# BSPD_Test_Board_rev2.net
KiCad netlist of a schematic drawn in EAGLE
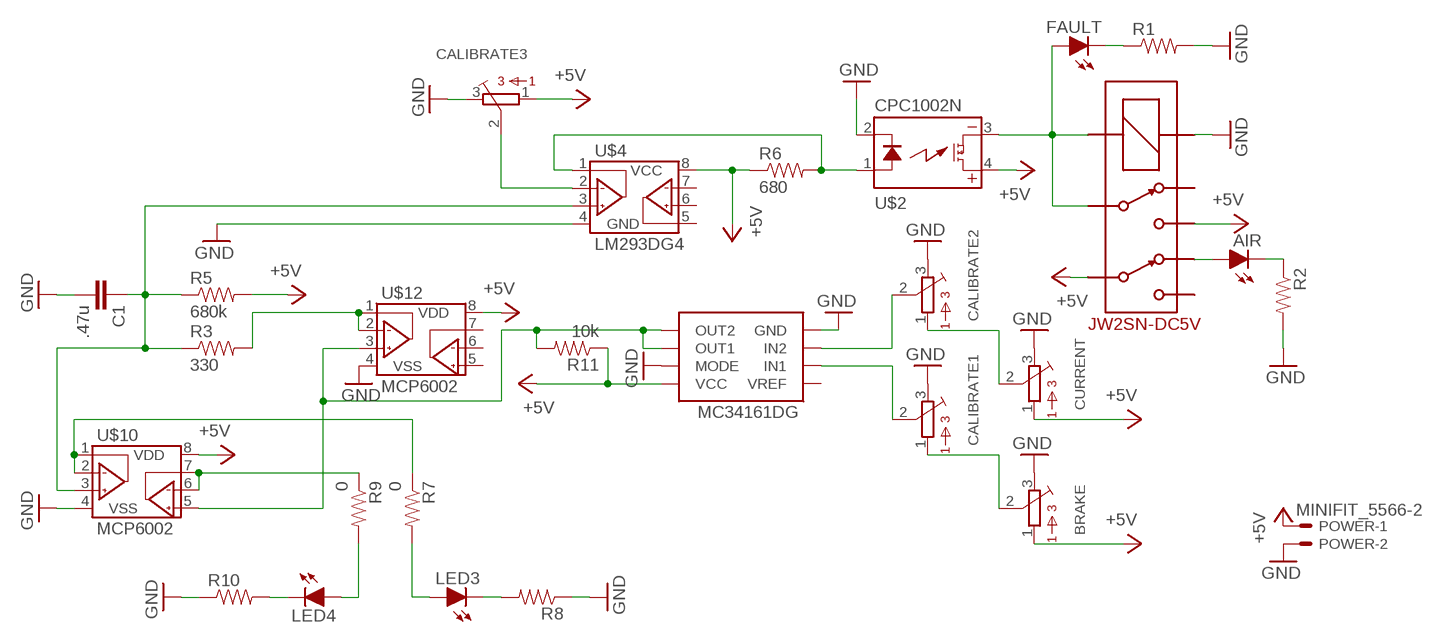
[diagram p0: schematic, sheet 1]

(export (version "E")
  (design (tool "Eeschema 10.0.6"))
  (components
    (comp (ref "AIR")
      (value "LED-5MM")
      (footprint "eagle-import:LED-5MM")
      (libsource (lib "eagle-import") (part "LED-5MM"))
    )
    (comp (ref "BRAKE")
      (value "TRIMPOT_3296C")
      (footprint "eagle-import:TRIMPOT_3296")
      (libsource (lib "eagle-import") (part "TRIMPOT_3296C"))
    )
    (comp (ref "C1")
      (value ".47u")
      (footprint "eagle-import:CAP-PTH-SMALLEZ")
      (libsource (lib "eagle-import") (part "CAPEZ"))
    )
    (comp (ref "CALIBRATE1")
      (value "TRIMPOT_3296C")
      (footprint "eagle-import:TRIMPOT_3296")
      (libsource (lib "eagle-import") (part "TRIMPOT_3296C"))
    )
    (comp (ref "CALIBRATE2")
      (value "TRIMPOT_3296C")
      (footprint "eagle-import:TRIMPOT_3296")
      (libsource (lib "eagle-import") (part "TRIMPOT_3296C"))
    )
    (comp (ref "CALIBRATE3")
      (value "TRIMPOT_3296C")
      (footprint "eagle-import:TRIMPOT_3296")
      (libsource (lib "eagle-import") (part "TRIMPOT_3296C"))
    )
    (comp (ref "CURRENT")
      (value "TRIMPOT_3296C")
      (footprint "eagle-import:TRIMPOT_3296")
      (libsource (lib "eagle-import") (part "TRIMPOT_3296C"))
    )
    (comp (ref "FAULT")
      (value "LED-5MM")
      (footprint "eagle-import:LED-5MM")
      (libsource (lib "eagle-import") (part "LED-5MM"))
    )
    (comp (ref "LED3")
      (value "LED-5MM")
      (footprint "eagle-import:LED-5MM")
      (libsource (lib "eagle-import") (part "LED-5MM"))
    )
    (comp (ref "LED4")
      (value "LED-5MM")
      (footprint "eagle-import:LED-5MM")
      (libsource (lib "eagle-import") (part "LED-5MM"))
    )
    (comp (ref "MC34161DG")
      (value "MC34161DG")
      (footprint "eagle-import:SOIC-08")
      (libsource (lib "eagle-import") (part "MC34161DG"))
    )
    (comp (ref "POWER")
      (value "MINIFIT_5566-2")
      (footprint "eagle-import:MINIFIT_5566-2")
      (libsource (lib "eagle-import") (part "MINIFIT_5566-2"))
    )
    (comp (ref "R1")
      (value "RESISTOR0805-RES")
      (footprint "eagle-import:0805")
      (libsource (lib "eagle-import") (part "RESISTOR0805-RES"))
    )
    (comp (ref "R2")
      (value "RESISTOR0805-RES")
      (footprint "eagle-import:0805")
      (libsource (lib "eagle-import") (part "RESISTOR0805-RES"))
    )
    (comp (ref "R3")
      (value "330")
      (footprint "eagle-import:AXIAL-0.3EZ")
      (libsource (lib "eagle-import") (part "RESISTOREZ"))
    )
    (comp (ref "R5")
      (value "680k")
      (footprint "eagle-import:AXIAL-0.3EZ")
      (libsource (lib "eagle-import") (part "RESISTOREZ"))
    )
    (comp (ref "R6")
      (value "680")
      (footprint "eagle-import:0805")
      (libsource (lib "eagle-import") (part "RESISTOR0805-RES"))
    )
    (comp (ref "R7")
      (value "0")
      (footprint "eagle-import:AXIAL-0.3EZ")
      (libsource (lib "eagle-import") (part "RESISTOREZ"))
    )
    (comp (ref "R8")
      (value "RESISTOR0805-RES")
      (footprint "eagle-import:0805")
      (libsource (lib "eagle-import") (part "RESISTOR0805-RES"))
    )
    (comp (ref "R9")
      (value "0")
      (footprint "eagle-import:AXIAL-0.3EZ")
      (libsource (lib "eagle-import") (part "RESISTOREZ"))
    )
    (comp (ref "R10")
      (value "RESISTOR0805-RES")
      (footprint "eagle-import:0805")
      (libsource (lib "eagle-import") (part "RESISTOR0805-RES"))
    )
    (comp (ref "R11")
      (value "10k")
      (footprint "eagle-import:0805")
      (libsource (lib "eagle-import") (part "RESISTOR0805-RES"))
    )
    (comp (ref "U$2")
      (value "CPC1002N")
      (footprint "eagle-import:SOP04")
      (libsource (lib "eagle-import") (part "CPC1002N"))
    )
    (comp (ref "U$3")
      (value "DPDT_RELAY_PANASONIC_JW2SN-DC5V")
      (footprint "eagle-import:DPDT_RELAY_PANASONIC_JW2SN")
      (libsource (lib "eagle-import") (part "DPDT_RELAY_PANASONIC_JW2SN-DC5V"))
    )
    (comp (ref "U$4")
      (value "LM293DG4")
      (footprint "eagle-import:SOIC-08")
      (libsource (lib "eagle-import") (part "LM293DG4"))
    )
    (comp (ref "U$10")
      (value "MCP6002")
      (footprint "eagle-import:SOIC-08")
      (libsource (lib "eagle-import") (part "MCP6002"))
    )
    (comp (ref "U$12")
      (value "MCP6002")
      (footprint "eagle-import:SOIC-08")
      (libsource (lib "eagle-import") (part "MCP6002"))
    )
  )
  (nets
    (net (code "1") (name "+5V") (class "Default")
      (node (ref "BRAKE") (pin "1") (pinfunction "1_1") (pintype "passive"))
      (node (ref "CALIBRATE3") (pin "1") (pinfunction "1_1") (pintype "passive"))
      (node (ref "CURRENT") (pin "1") (pinfunction "1_1") (pintype "passive"))
      (node (ref "MC34161DG") (pin "8") (pinfunction "VCC_8") (pintype "passive"))
      (node (ref "POWER") (pin "1") (pinfunction "S_1") (pintype "passive"))
      (node (ref "R11") (pin "1") (pinfunction "1_1") (pintype "passive"))
      (node (ref "R5") (pin "P$2") (pinfunction "2_P$2") (pintype "passive"))
      (node (ref "R6") (pin "1") (pinfunction "1_1") (pintype "passive"))
      (node (ref "U$10") (pin "8") (pinfunction "VDD_8") (pintype "passive"))
      (node (ref "U$12") (pin "8") (pinfunction "VDD_8") (pintype "passive"))
      (node (ref "U$2") (pin "4") (pinfunction "DC+_4") (pintype "passive"))
      (node (ref "U$3") (pin "4") (pinfunction "4_4") (pintype "bidirectional"))
      (node (ref "U$3") (pin "6") (pinfunction "6_6") (pintype "bidirectional"))
      (node (ref "U$4") (pin "8") (pinfunction "VCC_8") (pintype "passive"))
    )
    (net (code "2") (name "GND") (class "Default")
      (node (ref "BRAKE") (pin "3") (pinfunction "3_3") (pintype "passive"))
      (node (ref "C1") (pin "2") (pinfunction "2_2") (pintype "passive"))
      (node (ref "CALIBRATE1") (pin "3") (pinfunction "3_3") (pintype "passive"))
      (node (ref "CALIBRATE2") (pin "3") (pinfunction "3_3") (pintype "passive"))
      (node (ref "CALIBRATE3") (pin "3") (pinfunction "3_3") (pintype "passive"))
      (node (ref "CURRENT") (pin "3") (pinfunction "3_3") (pintype "passive"))
      (node (ref "MC34161DG") (pin "4") (pinfunction "GND_4") (pintype "passive"))
      (node (ref "MC34161DG") (pin "7") (pinfunction "MODE_7") (pintype "passive"))
      (node (ref "POWER") (pin "2") (pinfunction "S_2") (pintype "passive"))
      (node (ref "R1") (pin "2") (pinfunction "2_2") (pintype "passive"))
      (node (ref "R10") (pin "1") (pinfunction "1_1") (pintype "passive"))
      (node (ref "R2") (pin "2") (pinfunction "2_2") (pintype "passive"))
      (node (ref "R8") (pin "1") (pinfunction "1_1") (pintype "passive"))
      (node (ref "U$10") (pin "4") (pinfunction "VSS_4") (pintype "passive"))
      (node (ref "U$12") (pin "4") (pinfunction "VSS_4") (pintype "passive"))
      (node (ref "U$2") (pin "2") (pinfunction "CONTROL-_2") (pintype "passive"))
      (node (ref "U$3") (pin "COIL+") (pinfunction "COIL+_COIL+") (pintype "bidirectional"))
      (node (ref "U$4") (pin "4") (pinfunction "GND_4") (pintype "passive"))
    )
    (net (code "3") (name "Net-(AIR-C)") (class "Default")
      (node (ref "AIR") (pin "K") (pinfunction "C_K") (pintype "passive"))
      (node (ref "R2") (pin "1") (pinfunction "1_1") (pintype "passive"))
    )
    (net (code "4") (name "Net-(AIR-PadA)") (class "Default")
      (node (ref "AIR") (pin "A") (pinfunction "A_A") (pintype "passive"))
      (node (ref "U$3") (pin "7") (pinfunction "7_7") (pintype "bidirectional"))
    )
    (net (code "5") (name "Net-(BRAKE-Pad2)") (class "Default")
      (node (ref "BRAKE") (pin "2") (pinfunction "2_2") (pintype "passive"))
      (node (ref "CALIBRATE1") (pin "1") (pinfunction "1_1") (pintype "passive"))
    )
    (net (code "6") (name "Net-(CALIBRATE2-Pad1)") (class "Default")
      (node (ref "CALIBRATE2") (pin "1") (pinfunction "1_1") (pintype "passive"))
      (node (ref "CURRENT") (pin "2") (pinfunction "2_2") (pintype "passive"))
    )
    (net (code "7") (name "Net-(FAULT-C)") (class "Default")
      (node (ref "FAULT") (pin "K") (pinfunction "C_K") (pintype "passive"))
      (node (ref "R1") (pin "1") (pinfunction "1_1") (pintype "passive"))
    )
    (net (code "8") (name "Net-(LED3-C)") (class "Default")
      (node (ref "LED3") (pin "K") (pinfunction "C_K") (pintype "passive"))
      (node (ref "R8") (pin "2") (pinfunction "2_2") (pintype "passive"))
    )
    (net (code "9") (name "Net-(LED4-C)") (class "Default")
      (node (ref "LED4") (pin "K") (pinfunction "C_K") (pintype "passive"))
      (node (ref "R10") (pin "2") (pinfunction "2_2") (pintype "passive"))
    )
    (net (code "10") (name "Net-(MC34161DG-IN1)") (class "Default")
      (node (ref "CALIBRATE1") (pin "2") (pinfunction "2_2") (pintype "passive"))
      (node (ref "MC34161DG") (pin "2") (pinfunction "IN1_2") (pintype "passive"))
    )
    (net (code "11") (name "Net-(MC34161DG-IN2)") (class "Default")
      (node (ref "CALIBRATE2") (pin "2") (pinfunction "2_2") (pintype "passive"))
      (node (ref "MC34161DG") (pin "3") (pinfunction "IN2_3") (pintype "passive"))
    )
    (net (code "12") (name "Net-(MC34161DG-OUT1)") (class "Default")
      (node (ref "MC34161DG") (pin "5") (pinfunction "OUT2_5") (pintype "passive"))
      (node (ref "MC34161DG") (pin "6") (pinfunction "OUT1_6") (pintype "passive"))
      (node (ref "R11") (pin "2") (pinfunction "2_2") (pintype "passive"))
      (node (ref "U$10") (pin "5") (pinfunction "VINB+_5") (pintype "passive"))
      (node (ref "U$12") (pin "3") (pinfunction "VINA+_3") (pintype "passive"))
    )
    (net (code "13") (name "Net-(R3-1)") (class "Default")
      (node (ref "C1") (pin "1") (pinfunction "1_1") (pintype "passive"))
      (node (ref "R3") (pin "P$1") (pinfunction "1_P$1") (pintype "passive"))
      (node (ref "R5") (pin "P$1") (pinfunction "1_P$1") (pintype "passive"))
      (node (ref "U$10") (pin "3") (pinfunction "VINA+_3") (pintype "passive"))
      (node (ref "U$4") (pin "3") (pinfunction "1IN+_3") (pintype "passive"))
    )
    (net (code "14") (name "Net-(R3-2)") (class "Default")
      (node (ref "R3") (pin "P$2") (pinfunction "2_P$2") (pintype "passive"))
      (node (ref "U$12") (pin "1") (pinfunction "VOUTA_1") (pintype "passive"))
      (node (ref "U$12") (pin "2") (pinfunction "VINA-_2") (pintype "passive"))
    )
    (net (code "15") (name "Net-(R7-1)") (class "Default")
      (node (ref "R7") (pin "P$1") (pinfunction "1_P$1") (pintype "passive"))
      (node (ref "U$10") (pin "1") (pinfunction "VOUTA_1") (pintype "passive"))
      (node (ref "U$10") (pin "2") (pinfunction "VINA-_2") (pintype "passive"))
    )
    (net (code "16") (name "Net-(R7-2)") (class "Default")
      (node (ref "LED3") (pin "A") (pinfunction "A_A") (pintype "passive"))
      (node (ref "R7") (pin "P$2") (pinfunction "2_P$2") (pintype "passive"))
    )
    (net (code "17") (name "Net-(R9-1)") (class "Default")
      (node (ref "R9") (pin "P$1") (pinfunction "1_P$1") (pintype "passive"))
      (node (ref "U$10") (pin "6") (pinfunction "VINB-_6") (pintype "passive"))
      (node (ref "U$10") (pin "7") (pinfunction "VOUTB_7") (pintype "passive"))
    )
    (net (code "18") (name "Net-(R9-2)") (class "Default")
      (node (ref "LED4") (pin "A") (pinfunction "A_A") (pintype "passive"))
      (node (ref "R9") (pin "P$2") (pinfunction "2_P$2") (pintype "passive"))
    )
    (net (code "19") (name "Net-(U$2-CONTROL+)") (class "Default")
      (node (ref "R6") (pin "2") (pinfunction "2_2") (pintype "passive"))
      (node (ref "U$2") (pin "1") (pinfunction "CONTROL+_1") (pintype "passive"))
      (node (ref "U$4") (pin "1") (pinfunction "1OUT_1") (pintype "passive"))
    )
    (net (code "20") (name "Net-(U$2-DC-)") (class "Default")
      (node (ref "FAULT") (pin "A") (pinfunction "A_A") (pintype "passive"))
      (node (ref "U$2") (pin "3") (pinfunction "DC-_3") (pintype "passive"))
      (node (ref "U$3") (pin "3") (pinfunction "3_3") (pintype "bidirectional"))
      (node (ref "U$3") (pin "COIL-") (pinfunction "COIL-_COIL-") (pintype "bidirectional"))
    )
    (net (code "21") (name "Net-(U$4-1IN-)") (class "Default")
      (node (ref "CALIBRATE3") (pin "2") (pinfunction "2_2") (pintype "passive"))
      (node (ref "U$4") (pin "2") (pinfunction "1IN-_2") (pintype "passive"))
    )
    (net (code "22") (name "unconnected-(MC34161DG-VREF-Pad1)") (class "Default")
      (node (ref "MC34161DG") (pin "1") (pinfunction "VREF_1") (pintype "passive"))
    )
    (net (code "23") (name "unconnected-(U$3-Pad2)") (class "Default")
      (node (ref "U$3") (pin "2") (pinfunction "2_2") (pintype "bidirectional"))
    )
    (net (code "24") (name "unconnected-(U$3-Pad5)") (class "Default")
      (node (ref "U$3") (pin "5") (pinfunction "5_5") (pintype "bidirectional"))
    )
    (net (code "25") (name "unconnected-(U$4-2IN+-Pad5)") (class "Default")
      (node (ref "U$4") (pin "5") (pinfunction "2IN+_5") (pintype "passive"))
    )
    (net (code "26") (name "unconnected-(U$4-2IN--Pad6)") (class "Default")
      (node (ref "U$4") (pin "6") (pinfunction "2IN-_6") (pintype "passive"))
    )
    (net (code "27") (name "unconnected-(U$4-2OUT-Pad7)") (class "Default")
      (node (ref "U$4") (pin "7") (pinfunction "2OUT_7") (pintype "passive"))
    )
    (net (code "28") (name "unconnected-(U$12-VINB+-Pad5)") (class "Default")
      (node (ref "U$12") (pin "5") (pinfunction "VINB+_5") (pintype "passive"))
    )
    (net (code "29") (name "unconnected-(U$12-VINB--Pad6)") (class "Default")
      (node (ref "U$12") (pin "6") (pinfunction "VINB-_6") (pintype "passive"))
    )
    (net (code "30") (name "unconnected-(U$12-VOUTB-Pad7)") (class "Default")
      (node (ref "U$12") (pin "7") (pinfunction "VOUTB_7") (pintype "passive"))
    )
  )
)
